# NumatoShield.net
KiCad netlist of a schematic drawn in Altium Designer
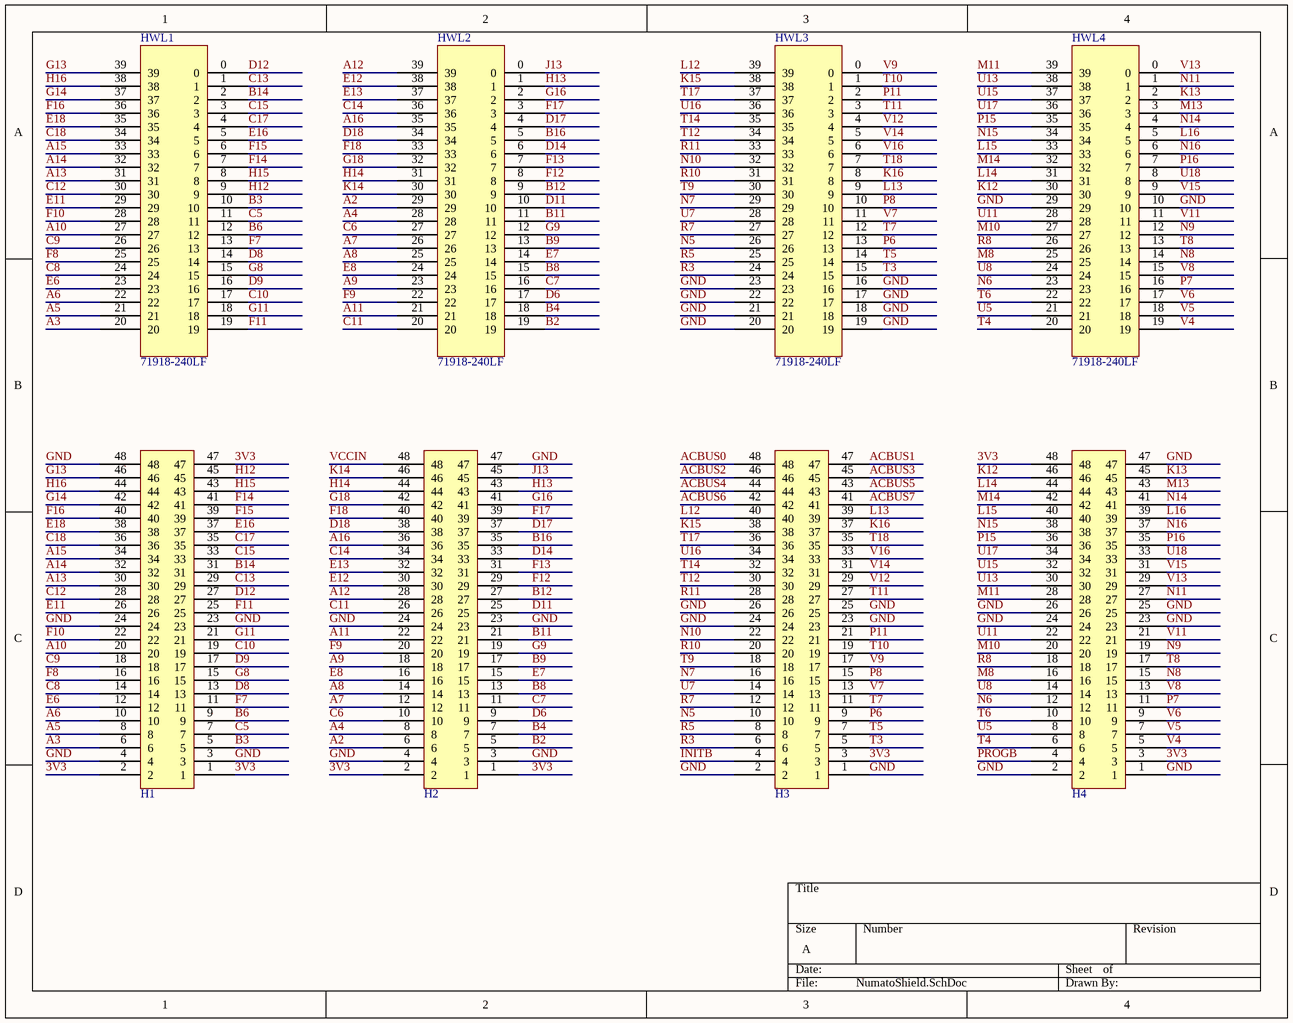
[diagram p0: NumatoShield.SchDoc]

(export (version "E")
  (design (tool "Eeschema 10.0.6"))
  (components
    (comp (ref "H1")
      (value "HEADER2X48")
      (footprint "H_FP")
      (libsource (lib "NumatoShield") (part "HEADER2X48"))
    )
    (comp (ref "H2")
      (value "HEADER2X48")
      (footprint "H_FP")
      (libsource (lib "NumatoShield") (part "HEADER2X48"))
    )
    (comp (ref "H3")
      (value "HEADER2X48")
      (footprint "H_FP")
      (libsource (lib "NumatoShield") (part "HEADER2X48"))
    )
    (comp (ref "H4")
      (value "HEADER2X48")
      (footprint "H_FP")
      (libsource (lib "NumatoShield") (part "HEADER2X48"))
    )
    (comp (ref "HWL1")
      (value "71918-240LF")
      (footprint "HWL_FP")
      (description "CONN HEADER 40POS DUAL VERT PCB")
      (fields (field (name "MANUFACTURER") "FCI") (field (name "MANUFACTURER PART NUMBER") "71918-240LF"))
      (libsource (lib "NumatoShield") (part "71918-240LF"))
    )
    (comp (ref "HWL2")
      (value "71918-240LF")
      (footprint "HWL_FP")
      (description "CONN HEADER 40POS DUAL VERT PCB")
      (fields (field (name "MANUFACTURER") "FCI") (field (name "MANUFACTURER PART NUMBER") "71918-240LF"))
      (libsource (lib "NumatoShield") (part "71918-240LF"))
    )
    (comp (ref "HWL3")
      (value "71918-240LF")
      (footprint "HWL_FP")
      (description "CONN HEADER 40POS DUAL VERT PCB")
      (fields (field (name "MANUFACTURER") "FCI") (field (name "MANUFACTURER PART NUMBER") "71918-240LF"))
      (libsource (lib "NumatoShield") (part "71918-240LF"))
    )
    (comp (ref "HWL4")
      (value "71918-240LF")
      (footprint "HWL_FP")
      (description "CONN HEADER 40POS DUAL VERT PCB")
      (fields (field (name "MANUFACTURER") "FCI") (field (name "MANUFACTURER PART NUMBER") "71918-240LF"))
      (libsource (lib "NumatoShield") (part "71918-240LF"))
    )
  )
  (nets
    (net (code "1") (name "/3V3") (class "Default")
      (node (ref "H1") (pin "1") (pinfunction "1_1") (pintype "passive"))
      (node (ref "H1") (pin "2") (pinfunction "2_2") (pintype "passive"))
      (node (ref "H1") (pin "47") (pinfunction "47_47") (pintype "passive"))
      (node (ref "H2") (pin "1") (pinfunction "1_1") (pintype "passive"))
      (node (ref "H2") (pin "2") (pinfunction "2_2") (pintype "passive"))
      (node (ref "H3") (pin "3") (pinfunction "3_3") (pintype "passive"))
      (node (ref "H4") (pin "3") (pinfunction "3_3") (pintype "passive"))
      (node (ref "H4") (pin "48") (pinfunction "48_48") (pintype "passive"))
    )
    (net (code "2") (name "/A2") (class "Default")
      (node (ref "H2") (pin "6") (pinfunction "6_6") (pintype "passive"))
      (node (ref "HWL2") (pin "29") (pinfunction "29_29") (pintype "passive"))
    )
    (net (code "3") (name "/A3") (class "Default")
      (node (ref "H1") (pin "6") (pinfunction "6_6") (pintype "passive"))
      (node (ref "HWL1") (pin "20") (pinfunction "20_20") (pintype "passive"))
    )
    (net (code "4") (name "/A4") (class "Default")
      (node (ref "H2") (pin "8") (pinfunction "8_8") (pintype "passive"))
      (node (ref "HWL2") (pin "28") (pinfunction "28_28") (pintype "passive"))
    )
    (net (code "5") (name "/A5") (class "Default")
      (node (ref "H1") (pin "8") (pinfunction "8_8") (pintype "passive"))
      (node (ref "HWL1") (pin "21") (pinfunction "21_21") (pintype "passive"))
    )
    (net (code "6") (name "/A6") (class "Default")
      (node (ref "H1") (pin "10") (pinfunction "10_10") (pintype "passive"))
      (node (ref "HWL1") (pin "22") (pinfunction "22_22") (pintype "passive"))
    )
    (net (code "7") (name "/A7") (class "Default")
      (node (ref "H2") (pin "12") (pinfunction "12_12") (pintype "passive"))
      (node (ref "HWL2") (pin "26") (pinfunction "26_26") (pintype "passive"))
    )
    (net (code "8") (name "/A8") (class "Default")
      (node (ref "H2") (pin "14") (pinfunction "14_14") (pintype "passive"))
      (node (ref "HWL2") (pin "25") (pinfunction "25_25") (pintype "passive"))
    )
    (net (code "9") (name "/A9") (class "Default")
      (node (ref "H2") (pin "18") (pinfunction "18_18") (pintype "passive"))
      (node (ref "HWL2") (pin "23") (pinfunction "23_23") (pintype "passive"))
    )
    (net (code "10") (name "/A10") (class "Default")
      (node (ref "H1") (pin "20") (pinfunction "20_20") (pintype "passive"))
      (node (ref "HWL1") (pin "27") (pinfunction "27_27") (pintype "passive"))
    )
    (net (code "11") (name "/A11") (class "Default")
      (node (ref "H2") (pin "22") (pinfunction "22_22") (pintype "passive"))
      (node (ref "HWL2") (pin "21") (pinfunction "21_21") (pintype "passive"))
    )
    (net (code "12") (name "/A12") (class "Default")
      (node (ref "H2") (pin "28") (pinfunction "28_28") (pintype "passive"))
      (node (ref "HWL2") (pin "39") (pinfunction "39_39") (pintype "passive"))
    )
    (net (code "13") (name "/A13") (class "Default")
      (node (ref "H1") (pin "30") (pinfunction "30_30") (pintype "passive"))
      (node (ref "HWL1") (pin "31") (pinfunction "31_31") (pintype "passive"))
    )
    (net (code "14") (name "/A14") (class "Default")
      (node (ref "H1") (pin "32") (pinfunction "32_32") (pintype "passive"))
      (node (ref "HWL1") (pin "32") (pinfunction "32_32") (pintype "passive"))
    )
    (net (code "15") (name "/A15") (class "Default")
      (node (ref "H1") (pin "34") (pinfunction "34_34") (pintype "passive"))
      (node (ref "HWL1") (pin "33") (pinfunction "33_33") (pintype "passive"))
    )
    (net (code "16") (name "/A16") (class "Default")
      (node (ref "H2") (pin "36") (pinfunction "36_36") (pintype "passive"))
      (node (ref "HWL2") (pin "35") (pinfunction "35_35") (pintype "passive"))
    )
    (net (code "17") (name "/ACBUS0") (class "Default")
      (node (ref "H3") (pin "48") (pinfunction "48_48") (pintype "passive"))
    )
    (net (code "18") (name "/ACBUS1") (class "Default")
      (node (ref "H3") (pin "47") (pinfunction "47_47") (pintype "passive"))
    )
    (net (code "19") (name "/ACBUS2") (class "Default")
      (node (ref "H3") (pin "46") (pinfunction "46_46") (pintype "passive"))
    )
    (net (code "20") (name "/ACBUS3") (class "Default")
      (node (ref "H3") (pin "45") (pinfunction "45_45") (pintype "passive"))
    )
    (net (code "21") (name "/ACBUS4") (class "Default")
      (node (ref "H3") (pin "44") (pinfunction "44_44") (pintype "passive"))
    )
    (net (code "22") (name "/ACBUS5") (class "Default")
      (node (ref "H3") (pin "43") (pinfunction "43_43") (pintype "passive"))
    )
    (net (code "23") (name "/ACBUS6") (class "Default")
      (node (ref "H3") (pin "42") (pinfunction "42_42") (pintype "passive"))
    )
    (net (code "24") (name "/ACBUS7") (class "Default")
      (node (ref "H3") (pin "41") (pinfunction "41_41") (pintype "passive"))
    )
    (net (code "25") (name "/B2") (class "Default")
      (node (ref "H2") (pin "5") (pinfunction "5_5") (pintype "passive"))
      (node (ref "HWL2") (pin "19") (pinfunction "19_19") (pintype "passive"))
    )
    (net (code "26") (name "/B3") (class "Default")
      (node (ref "H1") (pin "5") (pinfunction "5_5") (pintype "passive"))
      (node (ref "HWL1") (pin "10") (pinfunction "10_10") (pintype "passive"))
    )
    (net (code "27") (name "/B4") (class "Default")
      (node (ref "H2") (pin "7") (pinfunction "7_7") (pintype "passive"))
      (node (ref "HWL2") (pin "18") (pinfunction "18_18") (pintype "passive"))
    )
    (net (code "28") (name "/B6") (class "Default")
      (node (ref "H1") (pin "9") (pinfunction "9_9") (pintype "passive"))
      (node (ref "HWL1") (pin "12") (pinfunction "12_12") (pintype "passive"))
    )
    (net (code "29") (name "/B8") (class "Default")
      (node (ref "H2") (pin "13") (pinfunction "13_13") (pintype "passive"))
      (node (ref "HWL2") (pin "15") (pinfunction "15_15") (pintype "passive"))
    )
    (net (code "30") (name "/B9") (class "Default")
      (node (ref "H2") (pin "17") (pinfunction "17_17") (pintype "passive"))
      (node (ref "HWL2") (pin "13") (pinfunction "13_13") (pintype "passive"))
    )
    (net (code "31") (name "/B11") (class "Default")
      (node (ref "H2") (pin "21") (pinfunction "21_21") (pintype "passive"))
      (node (ref "HWL2") (pin "11") (pinfunction "11_11") (pintype "passive"))
    )
    (net (code "32") (name "/B12") (class "Default")
      (node (ref "H2") (pin "27") (pinfunction "27_27") (pintype "passive"))
      (node (ref "HWL2") (pin "9") (pinfunction "9_9") (pintype "passive"))
    )
    (net (code "33") (name "/B14") (class "Default")
      (node (ref "H1") (pin "31") (pinfunction "31_31") (pintype "passive"))
      (node (ref "HWL1") (pin "2") (pinfunction "2_2") (pintype "passive"))
    )
    (net (code "34") (name "/B16") (class "Default")
      (node (ref "H2") (pin "35") (pinfunction "35_35") (pintype "passive"))
      (node (ref "HWL2") (pin "5") (pinfunction "5_5") (pintype "passive"))
    )
    (net (code "35") (name "/C5") (class "Default")
      (node (ref "H1") (pin "7") (pinfunction "7_7") (pintype "passive"))
      (node (ref "HWL1") (pin "11") (pinfunction "11_11") (pintype "passive"))
    )
    (net (code "36") (name "/C6") (class "Default")
      (node (ref "H2") (pin "10") (pinfunction "10_10") (pintype "passive"))
      (node (ref "HWL2") (pin "27") (pinfunction "27_27") (pintype "passive"))
    )
    (net (code "37") (name "/C7") (class "Default")
      (node (ref "H2") (pin "11") (pinfunction "11_11") (pintype "passive"))
      (node (ref "HWL2") (pin "16") (pinfunction "16_16") (pintype "passive"))
    )
    (net (code "38") (name "/C8") (class "Default")
      (node (ref "H1") (pin "14") (pinfunction "14_14") (pintype "passive"))
      (node (ref "HWL1") (pin "24") (pinfunction "24_24") (pintype "passive"))
    )
    (net (code "39") (name "/C9") (class "Default")
      (node (ref "H1") (pin "18") (pinfunction "18_18") (pintype "passive"))
      (node (ref "HWL1") (pin "26") (pinfunction "26_26") (pintype "passive"))
    )
    (net (code "40") (name "/C10") (class "Default")
      (node (ref "H1") (pin "19") (pinfunction "19_19") (pintype "passive"))
      (node (ref "HWL1") (pin "17") (pinfunction "17_17") (pintype "passive"))
    )
    (net (code "41") (name "/C11") (class "Default")
      (node (ref "H2") (pin "26") (pinfunction "26_26") (pintype "passive"))
      (node (ref "HWL2") (pin "20") (pinfunction "20_20") (pintype "passive"))
    )
    (net (code "42") (name "/C12") (class "Default")
      (node (ref "H1") (pin "28") (pinfunction "28_28") (pintype "passive"))
      (node (ref "HWL1") (pin "30") (pinfunction "30_30") (pintype "passive"))
    )
    (net (code "43") (name "/C13") (class "Default")
      (node (ref "H1") (pin "29") (pinfunction "29_29") (pintype "passive"))
      (node (ref "HWL1") (pin "1") (pinfunction "1_1") (pintype "passive"))
    )
    (net (code "44") (name "/C14") (class "Default")
      (node (ref "H2") (pin "34") (pinfunction "34_34") (pintype "passive"))
      (node (ref "HWL2") (pin "36") (pinfunction "36_36") (pintype "passive"))
    )
    (net (code "45") (name "/C15") (class "Default")
      (node (ref "H1") (pin "33") (pinfunction "33_33") (pintype "passive"))
      (node (ref "HWL1") (pin "3") (pinfunction "3_3") (pintype "passive"))
    )
    (net (code "46") (name "/C17") (class "Default")
      (node (ref "H1") (pin "35") (pinfunction "35_35") (pintype "passive"))
      (node (ref "HWL1") (pin "4") (pinfunction "4_4") (pintype "passive"))
    )
    (net (code "47") (name "/C18") (class "Default")
      (node (ref "H1") (pin "36") (pinfunction "36_36") (pintype "passive"))
      (node (ref "HWL1") (pin "34") (pinfunction "34_34") (pintype "passive"))
    )
    (net (code "48") (name "/D6") (class "Default")
      (node (ref "H2") (pin "9") (pinfunction "9_9") (pintype "passive"))
      (node (ref "HWL2") (pin "17") (pinfunction "17_17") (pintype "passive"))
    )
    (net (code "49") (name "/D8") (class "Default")
      (node (ref "H1") (pin "13") (pinfunction "13_13") (pintype "passive"))
      (node (ref "HWL1") (pin "14") (pinfunction "14_14") (pintype "passive"))
    )
    (net (code "50") (name "/D9") (class "Default")
      (node (ref "H1") (pin "17") (pinfunction "17_17") (pintype "passive"))
      (node (ref "HWL1") (pin "16") (pinfunction "16_16") (pintype "passive"))
    )
    (net (code "51") (name "/D11") (class "Default")
      (node (ref "H2") (pin "25") (pinfunction "25_25") (pintype "passive"))
      (node (ref "HWL2") (pin "10") (pinfunction "10_10") (pintype "passive"))
    )
    (net (code "52") (name "/D12") (class "Default")
      (node (ref "H1") (pin "27") (pinfunction "27_27") (pintype "passive"))
      (node (ref "HWL1") (pin "0") (pinfunction "0_0") (pintype "passive"))
    )
    (net (code "53") (name "/D14") (class "Default")
      (node (ref "H2") (pin "33") (pinfunction "33_33") (pintype "passive"))
      (node (ref "HWL2") (pin "6") (pinfunction "6_6") (pintype "passive"))
    )
    (net (code "54") (name "/D17") (class "Default")
      (node (ref "H2") (pin "37") (pinfunction "37_37") (pintype "passive"))
      (node (ref "HWL2") (pin "4") (pinfunction "4_4") (pintype "passive"))
    )
    (net (code "55") (name "/D18") (class "Default")
      (node (ref "H2") (pin "38") (pinfunction "38_38") (pintype "passive"))
      (node (ref "HWL2") (pin "34") (pinfunction "34_34") (pintype "passive"))
    )
    (net (code "56") (name "/E6") (class "Default")
      (node (ref "H1") (pin "12") (pinfunction "12_12") (pintype "passive"))
      (node (ref "HWL1") (pin "23") (pinfunction "23_23") (pintype "passive"))
    )
    (net (code "57") (name "/E7") (class "Default")
      (node (ref "H2") (pin "15") (pinfunction "15_15") (pintype "passive"))
      (node (ref "HWL2") (pin "14") (pinfunction "14_14") (pintype "passive"))
    )
    (net (code "58") (name "/E8") (class "Default")
      (node (ref "H2") (pin "16") (pinfunction "16_16") (pintype "passive"))
      (node (ref "HWL2") (pin "24") (pinfunction "24_24") (pintype "passive"))
    )
    (net (code "59") (name "/E11") (class "Default")
      (node (ref "H1") (pin "26") (pinfunction "26_26") (pintype "passive"))
      (node (ref "HWL1") (pin "29") (pinfunction "29_29") (pintype "passive"))
    )
    (net (code "60") (name "/E12") (class "Default")
      (node (ref "H2") (pin "30") (pinfunction "30_30") (pintype "passive"))
      (node (ref "HWL2") (pin "38") (pinfunction "38_38") (pintype "passive"))
    )
    (net (code "61") (name "/E13") (class "Default")
      (node (ref "H2") (pin "32") (pinfunction "32_32") (pintype "passive"))
      (node (ref "HWL2") (pin "37") (pinfunction "37_37") (pintype "passive"))
    )
    (net (code "62") (name "/E16") (class "Default")
      (node (ref "H1") (pin "37") (pinfunction "37_37") (pintype "passive"))
      (node (ref "HWL1") (pin "5") (pinfunction "5_5") (pintype "passive"))
    )
    (net (code "63") (name "/E18") (class "Default")
      (node (ref "H1") (pin "38") (pinfunction "38_38") (pintype "passive"))
      (node (ref "HWL1") (pin "35") (pinfunction "35_35") (pintype "passive"))
    )
    (net (code "64") (name "/F7") (class "Default")
      (node (ref "H1") (pin "11") (pinfunction "11_11") (pintype "passive"))
      (node (ref "HWL1") (pin "13") (pinfunction "13_13") (pintype "passive"))
    )
    (net (code "65") (name "/F8") (class "Default")
      (node (ref "H1") (pin "16") (pinfunction "16_16") (pintype "passive"))
      (node (ref "HWL1") (pin "25") (pinfunction "25_25") (pintype "passive"))
    )
    (net (code "66") (name "/F9") (class "Default")
      (node (ref "H2") (pin "20") (pinfunction "20_20") (pintype "passive"))
      (node (ref "HWL2") (pin "22") (pinfunction "22_22") (pintype "passive"))
    )
    (net (code "67") (name "/F10") (class "Default")
      (node (ref "H1") (pin "22") (pinfunction "22_22") (pintype "passive"))
      (node (ref "HWL1") (pin "28") (pinfunction "28_28") (pintype "passive"))
    )
    (net (code "68") (name "/F11") (class "Default")
      (node (ref "H1") (pin "25") (pinfunction "25_25") (pintype "passive"))
      (node (ref "HWL1") (pin "19") (pinfunction "19_19") (pintype "passive"))
    )
    (net (code "69") (name "/F12") (class "Default")
      (node (ref "H2") (pin "29") (pinfunction "29_29") (pintype "passive"))
      (node (ref "HWL2") (pin "8") (pinfunction "8_8") (pintype "passive"))
    )
    (net (code "70") (name "/F13") (class "Default")
      (node (ref "H2") (pin "31") (pinfunction "31_31") (pintype "passive"))
      (node (ref "HWL2") (pin "7") (pinfunction "7_7") (pintype "passive"))
    )
    (net (code "71") (name "/F14") (class "Default")
      (node (ref "H1") (pin "41") (pinfunction "41_41") (pintype "passive"))
      (node (ref "HWL1") (pin "7") (pinfunction "7_7") (pintype "passive"))
    )
    (net (code "72") (name "/F15") (class "Default")
      (node (ref "H1") (pin "39") (pinfunction "39_39") (pintype "passive"))
      (node (ref "HWL1") (pin "6") (pinfunction "6_6") (pintype "passive"))
    )
    (net (code "73") (name "/F16") (class "Default")
      (node (ref "H1") (pin "40") (pinfunction "40_40") (pintype "passive"))
      (node (ref "HWL1") (pin "36") (pinfunction "36_36") (pintype "passive"))
    )
    (net (code "74") (name "/F17") (class "Default")
      (node (ref "H2") (pin "39") (pinfunction "39_39") (pintype "passive"))
      (node (ref "HWL2") (pin "3") (pinfunction "3_3") (pintype "passive"))
    )
    (net (code "75") (name "/F18") (class "Default")
      (node (ref "H2") (pin "40") (pinfunction "40_40") (pintype "passive"))
      (node (ref "HWL2") (pin "33") (pinfunction "33_33") (pintype "passive"))
    )
    (net (code "76") (name "/G8") (class "Default")
      (node (ref "H1") (pin "15") (pinfunction "15_15") (pintype "passive"))
      (node (ref "HWL1") (pin "15") (pinfunction "15_15") (pintype "passive"))
    )
    (net (code "77") (name "/G9") (class "Default")
      (node (ref "H2") (pin "19") (pinfunction "19_19") (pintype "passive"))
      (node (ref "HWL2") (pin "12") (pinfunction "12_12") (pintype "passive"))
    )
    (net (code "78") (name "/G11") (class "Default")
      (node (ref "H1") (pin "21") (pinfunction "21_21") (pintype "passive"))
      (node (ref "HWL1") (pin "18") (pinfunction "18_18") (pintype "passive"))
    )
    (net (code "79") (name "/G13") (class "Default")
      (node (ref "H1") (pin "46") (pinfunction "46_46") (pintype "passive"))
      (node (ref "HWL1") (pin "39") (pinfunction "39_39") (pintype "passive"))
    )
    (net (code "80") (name "/G14") (class "Default")
      (node (ref "H1") (pin "42") (pinfunction "42_42") (pintype "passive"))
      (node (ref "HWL1") (pin "37") (pinfunction "37_37") (pintype "passive"))
    )
    (net (code "81") (name "/G16") (class "Default")
      (node (ref "H2") (pin "41") (pinfunction "41_41") (pintype "passive"))
      (node (ref "HWL2") (pin "2") (pinfunction "2_2") (pintype "passive"))
    )
    (net (code "82") (name "/G18") (class "Default")
      (node (ref "H2") (pin "42") (pinfunction "42_42") (pintype "passive"))
      (node (ref "HWL2") (pin "32") (pinfunction "32_32") (pintype "passive"))
    )
    (net (code "83") (name "/GND") (class "Default")
      (node (ref "H1") (pin "23") (pinfunction "23_23") (pintype "passive"))
      (node (ref "H1") (pin "24") (pinfunction "24_24") (pintype "passive"))
      (node (ref "H1") (pin "3") (pinfunction "3_3") (pintype "passive"))
      (node (ref "H1") (pin "4") (pinfunction "4_4") (pintype "passive"))
      (node (ref "H1") (pin "48") (pinfunction "48_48") (pintype "passive"))
      (node (ref "H2") (pin "23") (pinfunction "23_23") (pintype "passive"))
      (node (ref "H2") (pin "24") (pinfunction "24_24") (pintype "passive"))
      (node (ref "H2") (pin "3") (pinfunction "3_3") (pintype "passive"))
      (node (ref "H2") (pin "4") (pinfunction "4_4") (pintype "passive"))
      (node (ref "H2") (pin "47") (pinfunction "47_47") (pintype "passive"))
      (node (ref "H3") (pin "1") (pinfunction "1_1") (pintype "passive"))
      (node (ref "H3") (pin "2") (pinfunction "2_2") (pintype "passive"))
      (node (ref "H3") (pin "23") (pinfunction "23_23") (pintype "passive"))
      (node (ref "H3") (pin "24") (pinfunction "24_24") (pintype "passive"))
      (node (ref "H3") (pin "25") (pinfunction "25_25") (pintype "passive"))
      (node (ref "H3") (pin "26") (pinfunction "26_26") (pintype "passive"))
      (node (ref "H4") (pin "1") (pinfunction "1_1") (pintype "passive"))
      (node (ref "H4") (pin "2") (pinfunction "2_2") (pintype "passive"))
      (node (ref "H4") (pin "23") (pinfunction "23_23") (pintype "passive"))
      (node (ref "H4") (pin "24") (pinfunction "24_24") (pintype "passive"))
      (node (ref "H4") (pin "25") (pinfunction "25_25") (pintype "passive"))
      (node (ref "H4") (pin "26") (pinfunction "26_26") (pintype "passive"))
      (node (ref "H4") (pin "47") (pinfunction "47_47") (pintype "passive"))
      (node (ref "HWL3") (pin "16") (pinfunction "16_16") (pintype "passive"))
      (node (ref "HWL3") (pin "17") (pinfunction "17_17") (pintype "passive"))
      (node (ref "HWL3") (pin "18") (pinfunction "18_18") (pintype "passive"))
      (node (ref "HWL3") (pin "19") (pinfunction "19_19") (pintype "passive"))
      (node (ref "HWL3") (pin "20") (pinfunction "20_20") (pintype "passive"))
      (node (ref "HWL3") (pin "21") (pinfunction "21_21") (pintype "passive"))
      (node (ref "HWL3") (pin "22") (pinfunction "22_22") (pintype "passive"))
      (node (ref "HWL3") (pin "23") (pinfunction "23_23") (pintype "passive"))
      (node (ref "HWL4") (pin "10") (pinfunction "10_10") (pintype "passive"))
      (node (ref "HWL4") (pin "29") (pinfunction "29_29") (pintype "passive"))
    )
    (net (code "84") (name "/H12") (class "Default")
      (node (ref "H1") (pin "45") (pinfunction "45_45") (pintype "passive"))
      (node (ref "HWL1") (pin "9") (pinfunction "9_9") (pintype "passive"))
    )
    (net (code "85") (name "/H13") (class "Default")
      (node (ref "H2") (pin "43") (pinfunction "43_43") (pintype "passive"))
      (node (ref "HWL2") (pin "1") (pinfunction "1_1") (pintype "passive"))
    )
    (net (code "86") (name "/H14") (class "Default")
      (node (ref "H2") (pin "44") (pinfunction "44_44") (pintype "passive"))
      (node (ref "HWL2") (pin "31") (pinfunction "31_31") (pintype "passive"))
    )
    (net (code "87") (name "/H15") (class "Default")
      (node (ref "H1") (pin "43") (pinfunction "43_43") (pintype "passive"))
      (node (ref "HWL1") (pin "8") (pinfunction "8_8") (pintype "passive"))
    )
    (net (code "88") (name "/H16") (class "Default")
      (node (ref "H1") (pin "44") (pinfunction "44_44") (pintype "passive"))
      (node (ref "HWL1") (pin "38") (pinfunction "38_38") (pintype "passive"))
    )
    (net (code "89") (name "/INITB") (class "Default")
      (node (ref "H3") (pin "4") (pinfunction "4_4") (pintype "passive"))
    )
    (net (code "90") (name "/J13") (class "Default")
      (node (ref "H2") (pin "45") (pinfunction "45_45") (pintype "passive"))
      (node (ref "HWL2") (pin "0") (pinfunction "0_0") (pintype "passive"))
    )
    (net (code "91") (name "/K12") (class "Default")
      (node (ref "H4") (pin "46") (pinfunction "46_46") (pintype "passive"))
      (node (ref "HWL4") (pin "30") (pinfunction "30_30") (pintype "passive"))
    )
    (net (code "92") (name "/K13") (class "Default")
      (node (ref "H4") (pin "45") (pinfunction "45_45") (pintype "passive"))
      (node (ref "HWL4") (pin "2") (pinfunction "2_2") (pintype "passive"))
    )
    (net (code "93") (name "/K14") (class "Default")
      (node (ref "H2") (pin "46") (pinfunction "46_46") (pintype "passive"))
      (node (ref "HWL2") (pin "30") (pinfunction "30_30") (pintype "passive"))
    )
    (net (code "94") (name "/K15") (class "Default")
      (node (ref "H3") (pin "38") (pinfunction "38_38") (pintype "passive"))
      (node (ref "HWL3") (pin "38") (pinfunction "38_38") (pintype "passive"))
    )
    (net (code "95") (name "/K16") (class "Default")
      (node (ref "H3") (pin "37") (pinfunction "37_37") (pintype "passive"))
      (node (ref "HWL3") (pin "8") (pinfunction "8_8") (pintype "passive"))
    )
    (net (code "96") (name "/L12") (class "Default")
      (node (ref "H3") (pin "40") (pinfunction "40_40") (pintype "passive"))
      (node (ref "HWL3") (pin "39") (pinfunction "39_39") (pintype "passive"))
    )
    (net (code "97") (name "/L13") (class "Default")
      (node (ref "H3") (pin "39") (pinfunction "39_39") (pintype "passive"))
      (node (ref "HWL3") (pin "9") (pinfunction "9_9") (pintype "passive"))
    )
    (net (code "98") (name "/L14") (class "Default")
      (node (ref "H4") (pin "44") (pinfunction "44_44") (pintype "passive"))
      (node (ref "HWL4") (pin "31") (pinfunction "31_31") (pintype "passive"))
    )
    (net (code "99") (name "/L15") (class "Default")
      (node (ref "H4") (pin "40") (pinfunction "40_40") (pintype "passive"))
      (node (ref "HWL4") (pin "33") (pinfunction "33_33") (pintype "passive"))
    )
    (net (code "100") (name "/L16") (class "Default")
      (node (ref "H4") (pin "39") (pinfunction "39_39") (pintype "passive"))
      (node (ref "HWL4") (pin "5") (pinfunction "5_5") (pintype "passive"))
    )
    (net (code "101") (name "/M8") (class "Default")
      (node (ref "H4") (pin "16") (pinfunction "16_16") (pintype "passive"))
      (node (ref "HWL4") (pin "25") (pinfunction "25_25") (pintype "passive"))
    )
    (net (code "102") (name "/M10") (class "Default")
      (node (ref "H4") (pin "20") (pinfunction "20_20") (pintype "passive"))
      (node (ref "HWL4") (pin "27") (pinfunction "27_27") (pintype "passive"))
    )
    (net (code "103") (name "/M11") (class "Default")
      (node (ref "H4") (pin "28") (pinfunction "28_28") (pintype "passive"))
      (node (ref "HWL4") (pin "39") (pinfunction "39_39") (pintype "passive"))
    )
    (net (code "104") (name "/M13") (class "Default")
      (node (ref "H4") (pin "43") (pinfunction "43_43") (pintype "passive"))
      (node (ref "HWL4") (pin "3") (pinfunction "3_3") (pintype "passive"))
    )
    (net (code "105") (name "/M14") (class "Default")
      (node (ref "H4") (pin "42") (pinfunction "42_42") (pintype "passive"))
      (node (ref "HWL4") (pin "32") (pinfunction "32_32") (pintype "passive"))
    )
    (net (code "106") (name "/N5") (class "Default")
      (node (ref "H3") (pin "10") (pinfunction "10_10") (pintype "passive"))
      (node (ref "HWL3") (pin "26") (pinfunction "26_26") (pintype "passive"))
    )
    (net (code "107") (name "/N6") (class "Default")
      (node (ref "H4") (pin "12") (pinfunction "12_12") (pintype "passive"))
      (node (ref "HWL4") (pin "23") (pinfunction "23_23") (pintype "passive"))
    )
    (net (code "108") (name "/N7") (class "Default")
      (node (ref "H3") (pin "16") (pinfunction "16_16") (pintype "passive"))
      (node (ref "HWL3") (pin "29") (pinfunction "29_29") (pintype "passive"))
    )
    (net (code "109") (name "/N8") (class "Default")
      (node (ref "H4") (pin "15") (pinfunction "15_15") (pintype "passive"))
      (node (ref "HWL4") (pin "14") (pinfunction "14_14") (pintype "passive"))
    )
    (net (code "110") (name "/N9") (class "Default")
      (node (ref "H4") (pin "19") (pinfunction "19_19") (pintype "passive"))
      (node (ref "HWL4") (pin "12") (pinfunction "12_12") (pintype "passive"))
    )
    (net (code "111") (name "/N10") (class "Default")
      (node (ref "H3") (pin "22") (pinfunction "22_22") (pintype "passive"))
      (node (ref "HWL3") (pin "32") (pinfunction "32_32") (pintype "passive"))
    )
    (net (code "112") (name "/N11") (class "Default")
      (node (ref "H4") (pin "27") (pinfunction "27_27") (pintype "passive"))
      (node (ref "HWL4") (pin "1") (pinfunction "1_1") (pintype "passive"))
    )
    (net (code "113") (name "/N14") (class "Default")
      (node (ref "H4") (pin "41") (pinfunction "41_41") (pintype "passive"))
      (node (ref "HWL4") (pin "4") (pinfunction "4_4") (pintype "passive"))
    )
    (net (code "114") (name "/N15") (class "Default")
      (node (ref "H4") (pin "38") (pinfunction "38_38") (pintype "passive"))
      (node (ref "HWL4") (pin "34") (pinfunction "34_34") (pintype "passive"))
    )
    (net (code "115") (name "/N16") (class "Default")
      (node (ref "H4") (pin "37") (pinfunction "37_37") (pintype "passive"))
      (node (ref "HWL4") (pin "6") (pinfunction "6_6") (pintype "passive"))
    )
    (net (code "116") (name "/P6") (class "Default")
      (node (ref "H3") (pin "9") (pinfunction "9_9") (pintype "passive"))
      (node (ref "HWL3") (pin "13") (pinfunction "13_13") (pintype "passive"))
    )
    (net (code "117") (name "/P7") (class "Default")
      (node (ref "H4") (pin "11") (pinfunction "11_11") (pintype "passive"))
      (node (ref "HWL4") (pin "16") (pinfunction "16_16") (pintype "passive"))
    )
    (net (code "118") (name "/P8") (class "Default")
      (node (ref "H3") (pin "15") (pinfunction "15_15") (pintype "passive"))
      (node (ref "HWL3") (pin "10") (pinfunction "10_10") (pintype "passive"))
    )
    (net (code "119") (name "/P11") (class "Default")
      (node (ref "H3") (pin "21") (pinfunction "21_21") (pintype "passive"))
      (node (ref "HWL3") (pin "2") (pinfunction "2_2") (pintype "passive"))
    )
    (net (code "120") (name "/P15") (class "Default")
      (node (ref "H4") (pin "36") (pinfunction "36_36") (pintype "passive"))
      (node (ref "HWL4") (pin "35") (pinfunction "35_35") (pintype "passive"))
    )
    (net (code "121") (name "/P16") (class "Default")
      (node (ref "H4") (pin "35") (pinfunction "35_35") (pintype "passive"))
      (node (ref "HWL4") (pin "7") (pinfunction "7_7") (pintype "passive"))
    )
    (net (code "122") (name "/PROGB") (class "Default")
      (node (ref "H4") (pin "4") (pinfunction "4_4") (pintype "passive"))
    )
    (net (code "123") (name "/R3") (class "Default")
      (node (ref "H3") (pin "6") (pinfunction "6_6") (pintype "passive"))
      (node (ref "HWL3") (pin "24") (pinfunction "24_24") (pintype "passive"))
    )
    (net (code "124") (name "/R5") (class "Default")
      (node (ref "H3") (pin "8") (pinfunction "8_8") (pintype "passive"))
      (node (ref "HWL3") (pin "25") (pinfunction "25_25") (pintype "passive"))
    )
    (net (code "125") (name "/R7") (class "Default")
      (node (ref "H3") (pin "12") (pinfunction "12_12") (pintype "passive"))
      (node (ref "HWL3") (pin "27") (pinfunction "27_27") (pintype "passive"))
    )
    (net (code "126") (name "/R8") (class "Default")
      (node (ref "H4") (pin "18") (pinfunction "18_18") (pintype "passive"))
      (node (ref "HWL4") (pin "26") (pinfunction "26_26") (pintype "passive"))
    )
    (net (code "127") (name "/R10") (class "Default")
      (node (ref "H3") (pin "20") (pinfunction "20_20") (pintype "passive"))
      (node (ref "HWL3") (pin "31") (pinfunction "31_31") (pintype "passive"))
    )
    (net (code "128") (name "/R11") (class "Default")
      (node (ref "H3") (pin "28") (pinfunction "28_28") (pintype "passive"))
      (node (ref "HWL3") (pin "33") (pinfunction "33_33") (pintype "passive"))
    )
    (net (code "129") (name "/T3") (class "Default")
      (node (ref "H3") (pin "5") (pinfunction "5_5") (pintype "passive"))
      (node (ref "HWL3") (pin "15") (pinfunction "15_15") (pintype "passive"))
    )
    (net (code "130") (name "/T4") (class "Default")
      (node (ref "H4") (pin "6") (pinfunction "6_6") (pintype "passive"))
      (node (ref "HWL4") (pin "20") (pinfunction "20_20") (pintype "passive"))
    )
    (net (code "131") (name "/T5") (class "Default")
      (node (ref "H3") (pin "7") (pinfunction "7_7") (pintype "passive"))
      (node (ref "HWL3") (pin "14") (pinfunction "14_14") (pintype "passive"))
    )
    (net (code "132") (name "/T6") (class "Default")
      (node (ref "H4") (pin "10") (pinfunction "10_10") (pintype "passive"))
      (node (ref "HWL4") (pin "22") (pinfunction "22_22") (pintype "passive"))
    )
    (net (code "133") (name "/T7") (class "Default")
      (node (ref "H3") (pin "11") (pinfunction "11_11") (pintype "passive"))
      (node (ref "HWL3") (pin "12") (pinfunction "12_12") (pintype "passive"))
    )
    (net (code "134") (name "/T8") (class "Default")
      (node (ref "H4") (pin "17") (pinfunction "17_17") (pintype "passive"))
      (node (ref "HWL4") (pin "13") (pinfunction "13_13") (pintype "passive"))
    )
    (net (code "135") (name "/T9") (class "Default")
      (node (ref "H3") (pin "18") (pinfunction "18_18") (pintype "passive"))
      (node (ref "HWL3") (pin "30") (pinfunction "30_30") (pintype "passive"))
    )
    (net (code "136") (name "/T10") (class "Default")
      (node (ref "H3") (pin "19") (pinfunction "19_19") (pintype "passive"))
      (node (ref "HWL3") (pin "1") (pinfunction "1_1") (pintype "passive"))
    )
    (net (code "137") (name "/T11") (class "Default")
      (node (ref "H3") (pin "27") (pinfunction "27_27") (pintype "passive"))
      (node (ref "HWL3") (pin "3") (pinfunction "3_3") (pintype "passive"))
    )
    (net (code "138") (name "/T12") (class "Default")
      (node (ref "H3") (pin "30") (pinfunction "30_30") (pintype "passive"))
      (node (ref "HWL3") (pin "34") (pinfunction "34_34") (pintype "passive"))
    )
    (net (code "139") (name "/T14") (class "Default")
      (node (ref "H3") (pin "32") (pinfunction "32_32") (pintype "passive"))
      (node (ref "HWL3") (pin "35") (pinfunction "35_35") (pintype "passive"))
    )
    (net (code "140") (name "/T17") (class "Default")
      (node (ref "H3") (pin "36") (pinfunction "36_36") (pintype "passive"))
      (node (ref "HWL3") (pin "37") (pinfunction "37_37") (pintype "passive"))
    )
    (net (code "141") (name "/T18") (class "Default")
      (node (ref "H3") (pin "35") (pinfunction "35_35") (pintype "passive"))
      (node (ref "HWL3") (pin "7") (pinfunction "7_7") (pintype "passive"))
    )
    (net (code "142") (name "/U5") (class "Default")
      (node (ref "H4") (pin "8") (pinfunction "8_8") (pintype "passive"))
      (node (ref "HWL4") (pin "21") (pinfunction "21_21") (pintype "passive"))
    )
    (net (code "143") (name "/U7") (class "Default")
      (node (ref "H3") (pin "14") (pinfunction "14_14") (pintype "passive"))
      (node (ref "HWL3") (pin "28") (pinfunction "28_28") (pintype "passive"))
    )
    (net (code "144") (name "/U8") (class "Default")
      (node (ref "H4") (pin "14") (pinfunction "14_14") (pintype "passive"))
      (node (ref "HWL4") (pin "24") (pinfunction "24_24") (pintype "passive"))
    )
    (net (code "145") (name "/U11") (class "Default")
      (node (ref "H4") (pin "22") (pinfunction "22_22") (pintype "passive"))
      (node (ref "HWL4") (pin "28") (pinfunction "28_28") (pintype "passive"))
    )
    (net (code "146") (name "/U13") (class "Default")
      (node (ref "H4") (pin "30") (pinfunction "30_30") (pintype "passive"))
      (node (ref "HWL4") (pin "38") (pinfunction "38_38") (pintype "passive"))
    )
    (net (code "147") (name "/U15") (class "Default")
      (node (ref "H4") (pin "32") (pinfunction "32_32") (pintype "passive"))
      (node (ref "HWL4") (pin "37") (pinfunction "37_37") (pintype "passive"))
    )
    (net (code "148") (name "/U16") (class "Default")
      (node (ref "H3") (pin "34") (pinfunction "34_34") (pintype "passive"))
      (node (ref "HWL3") (pin "36") (pinfunction "36_36") (pintype "passive"))
    )
    (net (code "149") (name "/U17") (class "Default")
      (node (ref "H4") (pin "34") (pinfunction "34_34") (pintype "passive"))
      (node (ref "HWL4") (pin "36") (pinfunction "36_36") (pintype "passive"))
    )
    (net (code "150") (name "/U18") (class "Default")
      (node (ref "H4") (pin "33") (pinfunction "33_33") (pintype "passive"))
      (node (ref "HWL4") (pin "8") (pinfunction "8_8") (pintype "passive"))
    )
    (net (code "151") (name "/V4") (class "Default")
      (node (ref "H4") (pin "5") (pinfunction "5_5") (pintype "passive"))
      (node (ref "HWL4") (pin "19") (pinfunction "19_19") (pintype "passive"))
    )
    (net (code "152") (name "/V5") (class "Default")
      (node (ref "H4") (pin "7") (pinfunction "7_7") (pintype "passive"))
      (node (ref "HWL4") (pin "18") (pinfunction "18_18") (pintype "passive"))
    )
    (net (code "153") (name "/V6") (class "Default")
      (node (ref "H4") (pin "9") (pinfunction "9_9") (pintype "passive"))
      (node (ref "HWL4") (pin "17") (pinfunction "17_17") (pintype "passive"))
    )
    (net (code "154") (name "/V7") (class "Default")
      (node (ref "H3") (pin "13") (pinfunction "13_13") (pintype "passive"))
      (node (ref "HWL3") (pin "11") (pinfunction "11_11") (pintype "passive"))
    )
    (net (code "155") (name "/V8") (class "Default")
      (node (ref "H4") (pin "13") (pinfunction "13_13") (pintype "passive"))
      (node (ref "HWL4") (pin "15") (pinfunction "15_15") (pintype "passive"))
    )
    (net (code "156") (name "/V9") (class "Default")
      (node (ref "H3") (pin "17") (pinfunction "17_17") (pintype "passive"))
      (node (ref "HWL3") (pin "0") (pinfunction "0_0") (pintype "passive"))
    )
    (net (code "157") (name "/V11") (class "Default")
      (node (ref "H4") (pin "21") (pinfunction "21_21") (pintype "passive"))
      (node (ref "HWL4") (pin "11") (pinfunction "11_11") (pintype "passive"))
    )
    (net (code "158") (name "/V12") (class "Default")
      (node (ref "H3") (pin "29") (pinfunction "29_29") (pintype "passive"))
      (node (ref "HWL3") (pin "4") (pinfunction "4_4") (pintype "passive"))
    )
    (net (code "159") (name "/V13") (class "Default")
      (node (ref "H4") (pin "29") (pinfunction "29_29") (pintype "passive"))
      (node (ref "HWL4") (pin "0") (pinfunction "0_0") (pintype "passive"))
    )
    (net (code "160") (name "/V14") (class "Default")
      (node (ref "H3") (pin "31") (pinfunction "31_31") (pintype "passive"))
      (node (ref "HWL3") (pin "5") (pinfunction "5_5") (pintype "passive"))
    )
    (net (code "161") (name "/V15") (class "Default")
      (node (ref "H4") (pin "31") (pinfunction "31_31") (pintype "passive"))
      (node (ref "HWL4") (pin "9") (pinfunction "9_9") (pintype "passive"))
    )
    (net (code "162") (name "/V16") (class "Default")
      (node (ref "H3") (pin "33") (pinfunction "33_33") (pintype "passive"))
      (node (ref "HWL3") (pin "6") (pinfunction "6_6") (pintype "passive"))
    )
    (net (code "163") (name "/VCCIN") (class "Default")
      (node (ref "H2") (pin "48") (pinfunction "48_48") (pintype "passive"))
    )
  )
)
